# node_led.net
KiCad netlist of a schematic drawn in EAGLE
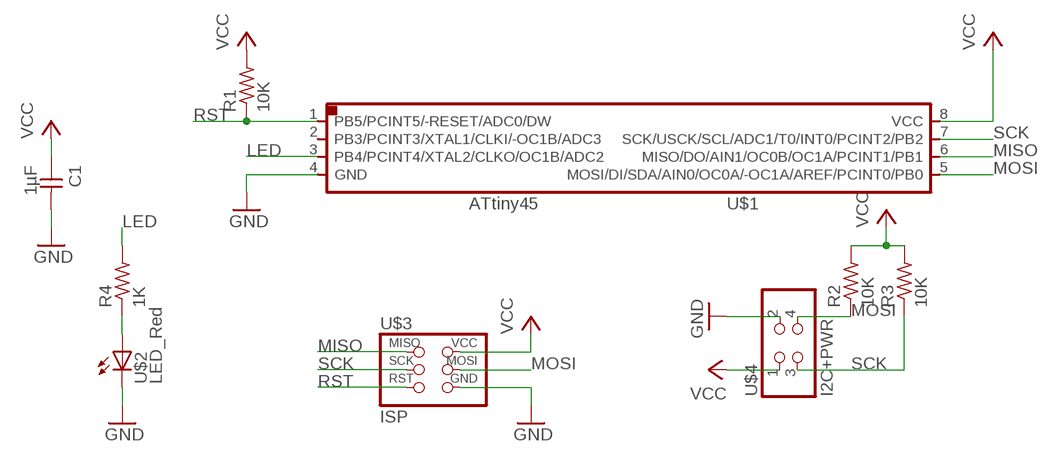
[diagram p0: schematic, sheet 1]

(export (version "E")
  (design (tool "Eeschema 10.0.6"))
  (components
    (comp (ref "C1")
      (value "1µF")
      (footprint "eagle-import:C1206FAB")
      (libsource (lib "eagle-import") (part "CAP-UNPOLARIZEDFAB"))
    )
    (comp (ref "R1")
      (value "10K")
      (footprint "eagle-import:R1206FAB")
      (libsource (lib "eagle-import") (part "RES-US1206FAB"))
    )
    (comp (ref "R2")
      (value "10K")
      (footprint "eagle-import:R1206FAB")
      (libsource (lib "eagle-import") (part "RES-US1206FAB"))
    )
    (comp (ref "R3")
      (value "10K")
      (footprint "eagle-import:R1206FAB")
      (libsource (lib "eagle-import") (part "RES-US1206FAB"))
    )
    (comp (ref "R4")
      (value "1K")
      (footprint "eagle-import:R1206FAB")
      (libsource (lib "eagle-import") (part "RES-US1206FAB"))
    )
    (comp (ref "U$1")
      (value "ATTINY45SI")
      (footprint "eagle-import:SOIC8")
      (libsource (lib "eagle-import") (part "ATTINY45SI"))
    )
    (comp (ref "U$2")
      (value "LED_Red")
      (footprint "eagle-import:LED1206FAB")
      (libsource (lib "eagle-import") (part "LEDFAB1206"))
    )
    (comp (ref "U$3")
      (value "ISP")
      (footprint "eagle-import:2X03SMD")
      (libsource (lib "eagle-import") (part "AVRISPSMD"))
    )
    (comp (ref "U$4")
      (value "I2C+PWR")
      (footprint "eagle-import:2X02SMD")
      (libsource (lib "eagle-import") (part "PINHD-2X2-SMD"))
    )
  )
  (nets
    (net (code "1") (name "/LED") (class "Default")
      (node (ref "R4") (pin "2") (pinfunction "2_2") (pintype "passive"))
      (node (ref "U$1") (pin "3") (pinfunction "PB4/PCINT4/XTAL2/CLKO/OC1B/ADC2_3") (pintype "bidirectional"))
    )
    (net (code "2") (name "/MISO") (class "Default")
      (node (ref "U$1") (pin "6") (pinfunction "MISO/DO/AIN1/OC0B/OC1A/PCINT1/PB1_6") (pintype "bidirectional"))
      (node (ref "U$3") (pin "1") (pinfunction "MISO_1") (pintype "passive"))
    )
    (net (code "3") (name "/MOSI") (class "Default")
      (node (ref "R2") (pin "1") (pinfunction "1_1") (pintype "passive"))
      (node (ref "U$1") (pin "5") (pinfunction "MOSI/DI/SDA/AIN0/OC0A/-OC1A/AREF/PCINT0/PB0_5") (pintype "bidirectional"))
      (node (ref "U$3") (pin "4") (pinfunction "MOSI_4") (pintype "passive"))
      (node (ref "U$4") (pin "4") (pinfunction "4_4") (pintype "passive"))
    )
    (net (code "4") (name "/RST") (class "Default")
      (node (ref "R1") (pin "1") (pinfunction "1_1") (pintype "passive"))
      (node (ref "U$1") (pin "1") (pinfunction "PB5/PCINT5/-RESET/ADC0/DW_1") (pintype "bidirectional"))
      (node (ref "U$3") (pin "5") (pinfunction "RST_5") (pintype "passive"))
    )
    (net (code "5") (name "/SCK") (class "Default")
      (node (ref "R3") (pin "1") (pinfunction "1_1") (pintype "passive"))
      (node (ref "U$1") (pin "7") (pinfunction "SCK/USCK/SCL/ADC1/T0/INT0/PCINT2/PB2_7") (pintype "bidirectional"))
      (node (ref "U$3") (pin "3") (pinfunction "SCK_3") (pintype "passive"))
      (node (ref "U$4") (pin "3") (pinfunction "3_3") (pintype "passive"))
    )
    (net (code "6") (name "GND") (class "Default")
      (node (ref "C1") (pin "2") (pinfunction "2_2") (pintype "passive"))
      (node (ref "U$1") (pin "4") (pinfunction "GND_4") (pintype "bidirectional"))
      (node (ref "U$2") (pin "2") (pinfunction "C_2") (pintype "passive"))
      (node (ref "U$3") (pin "6") (pinfunction "GND_6") (pintype "passive"))
      (node (ref "U$4") (pin "2") (pinfunction "2_2") (pintype "passive"))
    )
    (net (code "7") (name "Net-(U$2-A)") (class "Default")
      (node (ref "R4") (pin "1") (pinfunction "1_1") (pintype "passive"))
      (node (ref "U$2") (pin "1") (pinfunction "A_1") (pintype "passive"))
    )
    (net (code "8") (name "VCC") (class "Default")
      (node (ref "C1") (pin "1") (pinfunction "1_1") (pintype "passive"))
      (node (ref "R1") (pin "2") (pinfunction "2_2") (pintype "passive"))
      (node (ref "R2") (pin "2") (pinfunction "2_2") (pintype "passive"))
      (node (ref "R3") (pin "2") (pinfunction "2_2") (pintype "passive"))
      (node (ref "U$1") (pin "8") (pinfunction "VCC_8") (pintype "bidirectional"))
      (node (ref "U$3") (pin "2") (pinfunction "VCC_2") (pintype "passive"))
      (node (ref "U$4") (pin "1") (pinfunction "1_1") (pintype "passive"))
    )
    (net (code "9") (name "unconnected-(U$1-PB3{slash}PCINT3{slash}XTAL1{slash}CLKI{slash}-OC1B{slash}ADC3-Pad2)") (class "Default")
      (node (ref "U$1") (pin "2") (pinfunction "PB3/PCINT3/XTAL1/CLKI/-OC1B/ADC3_2") (pintype "bidirectional"))
    )
  )
)
